# open-race-scale-pi-zero-board-v_04.net
KiCad netlist of a schematic drawn in EAGLE
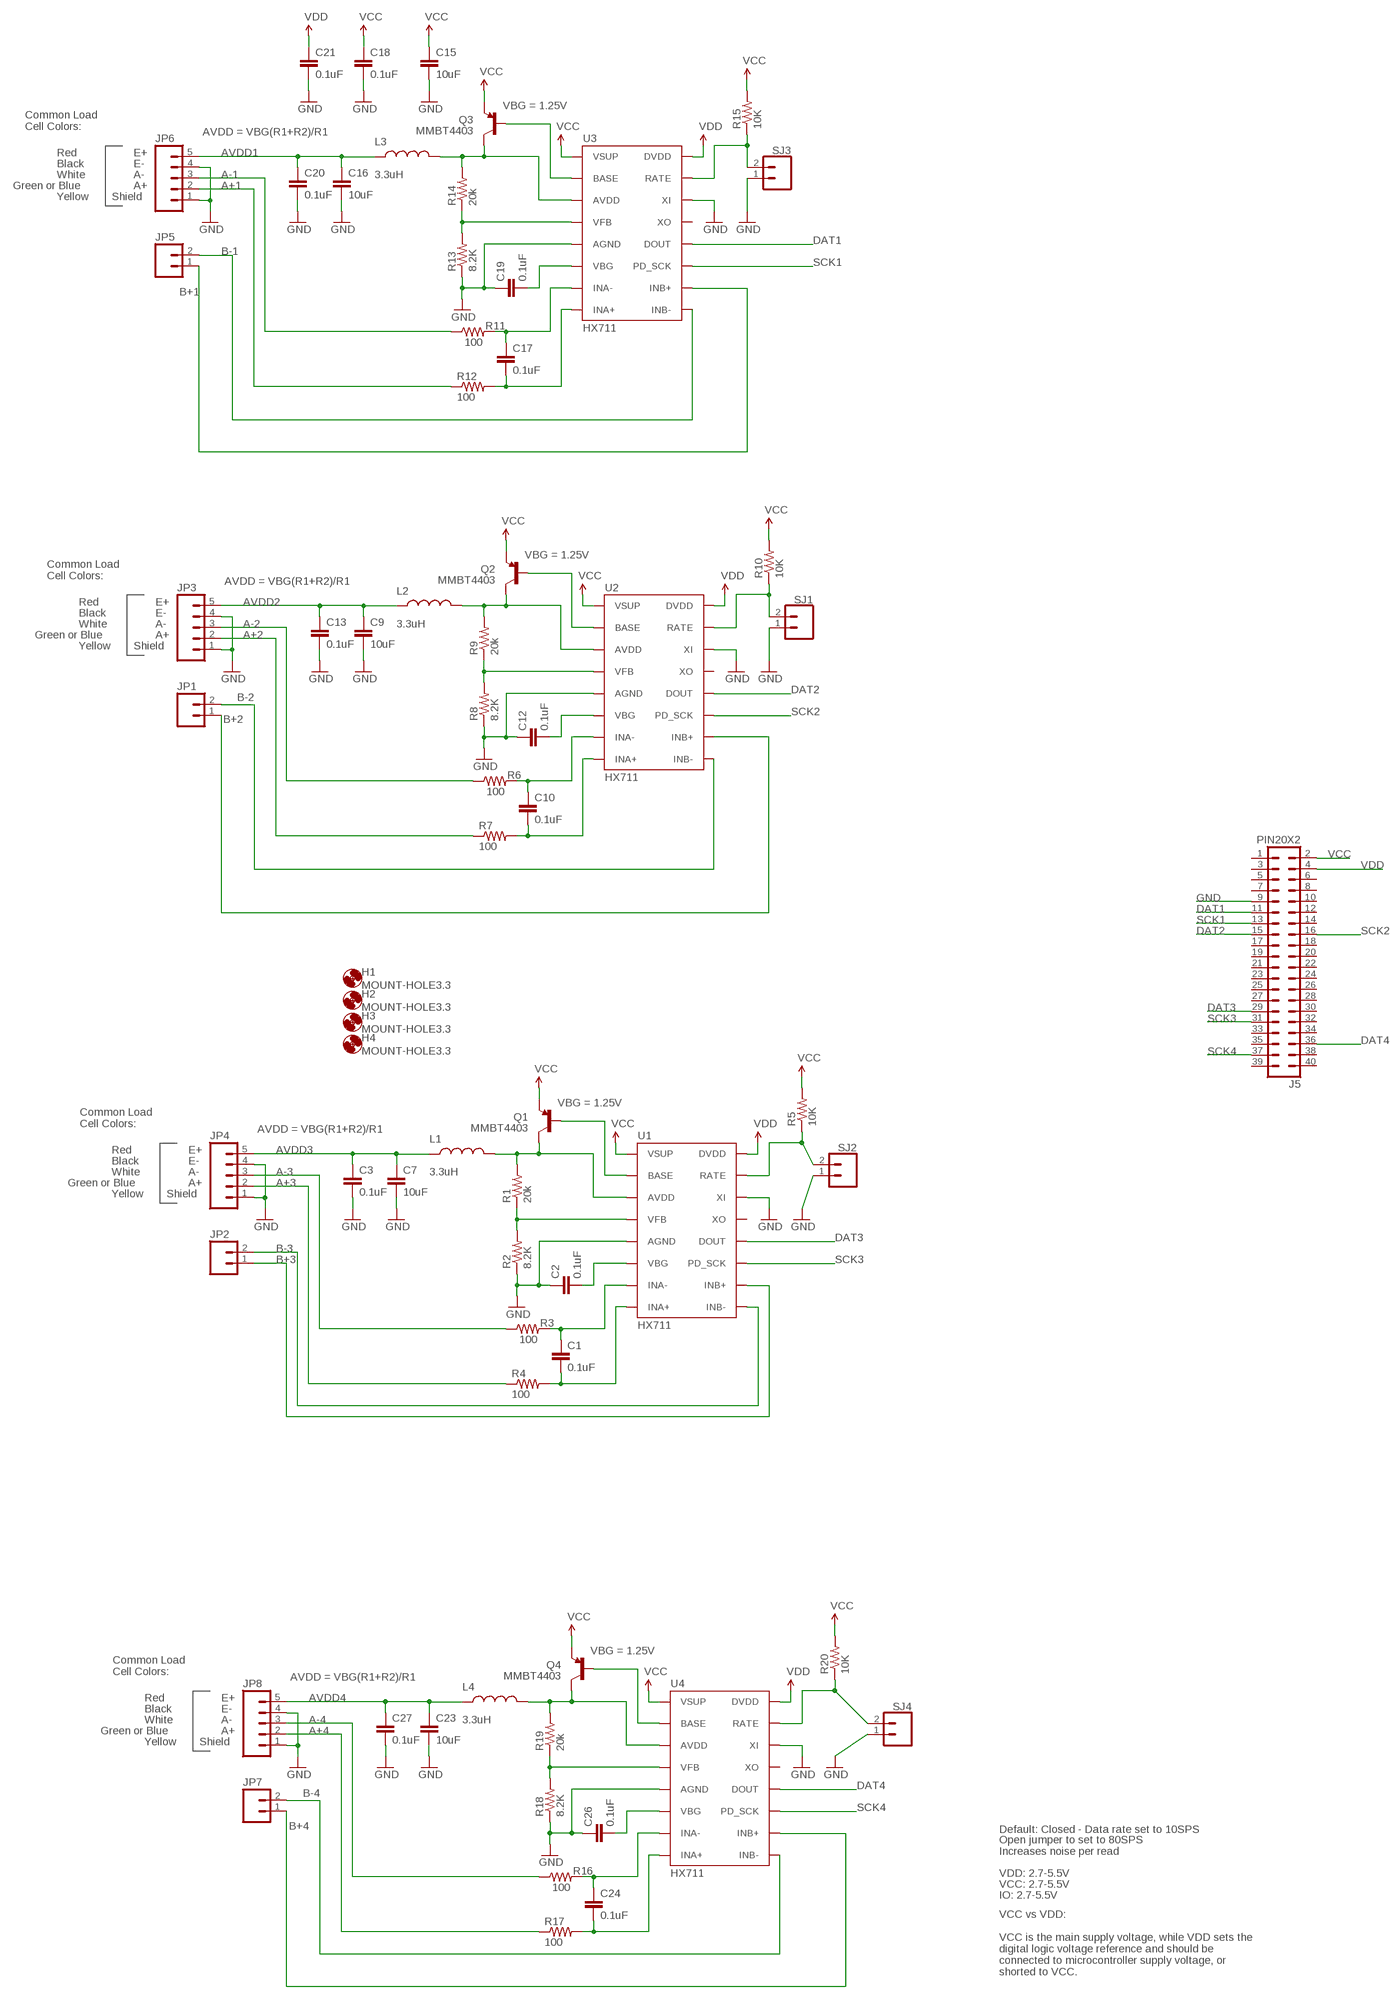
[diagram p0: schematic, sheet 1]

(export (version "E")
  (design (tool "Eeschema 10.0.6"))
  (components
    (comp (ref "C1")
      (value "0.1uF")
      (footprint "eagle-import:0603-CAP")
      (libsource (lib "eagle-import") (part "0.1UF-25V-5%(0603)"))
    )
    (comp (ref "C2")
      (value "0.1uF")
      (footprint "eagle-import:0603-CAP")
      (libsource (lib "eagle-import") (part "0.1UF-25V-5%(0603)"))
    )
    (comp (ref "C3")
      (value "0.1uF")
      (footprint "eagle-import:0603-CAP")
      (libsource (lib "eagle-import") (part "0.1UF-25V-5%(0603)"))
    )
    (comp (ref "C7")
      (value "10uF")
      (footprint "eagle-import:1210")
      (libsource (lib "eagle-import") (part "10UF50V20%(1210)"))
    )
    (comp (ref "C9")
      (value "10uF")
      (footprint "eagle-import:1210")
      (libsource (lib "eagle-import") (part "10UF50V20%(1210)"))
    )
    (comp (ref "C10")
      (value "0.1uF")
      (footprint "eagle-import:0603-CAP")
      (libsource (lib "eagle-import") (part "0.1UF-25V-5%(0603)"))
    )
    (comp (ref "C12")
      (value "0.1uF")
      (footprint "eagle-import:0603-CAP")
      (libsource (lib "eagle-import") (part "0.1UF-25V-5%(0603)"))
    )
    (comp (ref "C13")
      (value "0.1uF")
      (footprint "eagle-import:0603-CAP")
      (libsource (lib "eagle-import") (part "0.1UF-25V-5%(0603)"))
    )
    (comp (ref "C15")
      (value "10uF")
      (footprint "eagle-import:1210")
      (libsource (lib "eagle-import") (part "10UF50V20%(1210)"))
    )
    (comp (ref "C16")
      (value "10uF")
      (footprint "eagle-import:1210")
      (libsource (lib "eagle-import") (part "10UF50V20%(1210)"))
    )
    (comp (ref "C17")
      (value "0.1uF")
      (footprint "eagle-import:0603-CAP")
      (libsource (lib "eagle-import") (part "0.1UF-25V-5%(0603)"))
    )
    (comp (ref "C18")
      (value "0.1uF")
      (footprint "eagle-import:0603-CAP")
      (libsource (lib "eagle-import") (part "0.1UF-25V-5%(0603)"))
    )
    (comp (ref "C19")
      (value "0.1uF")
      (footprint "eagle-import:0603-CAP")
      (libsource (lib "eagle-import") (part "0.1UF-25V-5%(0603)"))
    )
    (comp (ref "C20")
      (value "0.1uF")
      (footprint "eagle-import:0603-CAP")
      (libsource (lib "eagle-import") (part "0.1UF-25V-5%(0603)"))
    )
    (comp (ref "C21")
      (value "0.1uF")
      (footprint "eagle-import:0603-CAP")
      (libsource (lib "eagle-import") (part "0.1UF-25V-5%(0603)"))
    )
    (comp (ref "C23")
      (value "10uF")
      (footprint "eagle-import:1210")
      (libsource (lib "eagle-import") (part "10UF50V20%(1210)"))
    )
    (comp (ref "C24")
      (value "0.1uF")
      (footprint "eagle-import:0603-CAP")
      (libsource (lib "eagle-import") (part "0.1UF-25V-5%(0603)"))
    )
    (comp (ref "C26")
      (value "0.1uF")
      (footprint "eagle-import:0603-CAP")
      (libsource (lib "eagle-import") (part "0.1UF-25V-5%(0603)"))
    )
    (comp (ref "C27")
      (value "0.1uF")
      (footprint "eagle-import:0603-CAP")
      (libsource (lib "eagle-import") (part "0.1UF-25V-5%(0603)"))
    )
    (comp (ref "H1")
      (value "MOUNT-HOLE3.3")
      (footprint "eagle-import:3,3")
      (libsource (lib "eagle-import") (part "MOUNT-HOLE3.3"))
    )
    (comp (ref "H2")
      (value "MOUNT-HOLE3.3")
      (footprint "eagle-import:3,3")
      (libsource (lib "eagle-import") (part "MOUNT-HOLE3.3"))
    )
    (comp (ref "H3")
      (value "MOUNT-HOLE3.3")
      (footprint "eagle-import:3,3")
      (libsource (lib "eagle-import") (part "MOUNT-HOLE3.3"))
    )
    (comp (ref "H4")
      (value "MOUNT-HOLE3.3")
      (footprint "eagle-import:3,3")
      (libsource (lib "eagle-import") (part "MOUNT-HOLE3.3"))
    )
    (comp (ref "J5")
      (value "PIN20X2")
      (footprint "eagle-import:PIN_20X2")
      (libsource (lib "eagle-import") (part "PIN20X2"))
    )
    (comp (ref "JP1")
      (value "M02PTH")
      (footprint "eagle-import:1X02@1")
      (libsource (lib "eagle-import") (part "M02PTH"))
    )
    (comp (ref "JP2")
      (value "M02PTH")
      (footprint "eagle-import:1X02@1")
      (libsource (lib "eagle-import") (part "M02PTH"))
    )
    (comp (ref "JP3")
      (value "M05PTH")
      (footprint "eagle-import:1X05")
      (libsource (lib "eagle-import") (part "M05PTH"))
    )
    (comp (ref "JP4")
      (value "M05PTH")
      (footprint "eagle-import:1X05")
      (libsource (lib "eagle-import") (part "M05PTH"))
    )
    (comp (ref "JP5")
      (value "M02PTH")
      (footprint "eagle-import:1X02@1")
      (libsource (lib "eagle-import") (part "M02PTH"))
    )
    (comp (ref "JP6")
      (value "M05PTH")
      (footprint "eagle-import:1X05")
      (libsource (lib "eagle-import") (part "M05PTH"))
    )
    (comp (ref "JP7")
      (value "M02PTH")
      (footprint "eagle-import:1X02@1")
      (libsource (lib "eagle-import") (part "M02PTH"))
    )
    (comp (ref "JP8")
      (value "M05PTH")
      (footprint "eagle-import:1X05")
      (libsource (lib "eagle-import") (part "M05PTH"))
    )
    (comp (ref "L1")
      (value "3.3uH")
      (footprint "eagle-import:0805")
      (libsource (lib "eagle-import") (part "INDUCTOR0805-IND"))
    )
    (comp (ref "L2")
      (value "3.3uH")
      (footprint "eagle-import:0805")
      (libsource (lib "eagle-import") (part "INDUCTOR0805-IND"))
    )
    (comp (ref "L3")
      (value "3.3uH")
      (footprint "eagle-import:0805")
      (libsource (lib "eagle-import") (part "INDUCTOR0805-IND"))
    )
    (comp (ref "L4")
      (value "3.3uH")
      (footprint "eagle-import:0805")
      (libsource (lib "eagle-import") (part "INDUCTOR0805-IND"))
    )
    (comp (ref "Q1")
      (value "MMBT4403")
      (footprint "eagle-import:SOT23-3")
      (libsource (lib "eagle-import") (part "TRANSISTOR_PNPMMBT4403"))
    )
    (comp (ref "Q2")
      (value "MMBT4403")
      (footprint "eagle-import:SOT23-3")
      (libsource (lib "eagle-import") (part "TRANSISTOR_PNPMMBT4403"))
    )
    (comp (ref "Q3")
      (value "MMBT4403")
      (footprint "eagle-import:SOT23-3")
      (libsource (lib "eagle-import") (part "TRANSISTOR_PNPMMBT4403"))
    )
    (comp (ref "Q4")
      (value "MMBT4403")
      (footprint "eagle-import:SOT23-3")
      (libsource (lib "eagle-import") (part "TRANSISTOR_PNPMMBT4403"))
    )
    (comp (ref "R1")
      (value "20k")
      (footprint "eagle-import:0603-RES")
      (libsource (lib "eagle-import") (part "20KOHM1/10W1%(0603)"))
    )
    (comp (ref "R2")
      (value "8.2K")
      (footprint "eagle-import:0603-RES")
      (libsource (lib "eagle-import") (part "8.2KOHM-1/10W-5%(0603)"))
    )
    (comp (ref "R3")
      (value "100")
      (footprint "eagle-import:0603-RES")
      (libsource (lib "eagle-import") (part "100OHM-1/10W-1%(0603)"))
    )
    (comp (ref "R4")
      (value "100")
      (footprint "eagle-import:0603-RES")
      (libsource (lib "eagle-import") (part "100OHM-1/10W-1%(0603)"))
    )
    (comp (ref "R5")
      (value "10K")
      (footprint "eagle-import:0603-RES")
      (libsource (lib "eagle-import") (part "10KOHM-1/10W-1%(0603)0603"))
    )
    (comp (ref "R6")
      (value "100")
      (footprint "eagle-import:0603-RES")
      (libsource (lib "eagle-import") (part "100OHM-1/10W-1%(0603)"))
    )
    (comp (ref "R7")
      (value "100")
      (footprint "eagle-import:0603-RES")
      (libsource (lib "eagle-import") (part "100OHM-1/10W-1%(0603)"))
    )
    (comp (ref "R8")
      (value "8.2K")
      (footprint "eagle-import:0603-RES")
      (libsource (lib "eagle-import") (part "8.2KOHM-1/10W-5%(0603)"))
    )
    (comp (ref "R9")
      (value "20k")
      (footprint "eagle-import:0603-RES")
      (libsource (lib "eagle-import") (part "20KOHM1/10W1%(0603)"))
    )
    (comp (ref "R10")
      (value "10K")
      (footprint "eagle-import:0603-RES")
      (libsource (lib "eagle-import") (part "10KOHM-1/10W-1%(0603)0603"))
    )
    (comp (ref "R11")
      (value "100")
      (footprint "eagle-import:0603-RES")
      (libsource (lib "eagle-import") (part "100OHM-1/10W-1%(0603)"))
    )
    (comp (ref "R12")
      (value "100")
      (footprint "eagle-import:0603-RES")
      (libsource (lib "eagle-import") (part "100OHM-1/10W-1%(0603)"))
    )
    (comp (ref "R13")
      (value "8.2K")
      (footprint "eagle-import:0603-RES")
      (libsource (lib "eagle-import") (part "8.2KOHM-1/10W-5%(0603)"))
    )
    (comp (ref "R14")
      (value "20k")
      (footprint "eagle-import:0603-RES")
      (libsource (lib "eagle-import") (part "20KOHM1/10W1%(0603)"))
    )
    (comp (ref "R15")
      (value "10K")
      (footprint "eagle-import:0603-RES")
      (libsource (lib "eagle-import") (part "10KOHM-1/10W-1%(0603)0603"))
    )
    (comp (ref "R16")
      (value "100")
      (footprint "eagle-import:0603-RES")
      (libsource (lib "eagle-import") (part "100OHM-1/10W-1%(0603)"))
    )
    (comp (ref "R17")
      (value "100")
      (footprint "eagle-import:0603-RES")
      (libsource (lib "eagle-import") (part "100OHM-1/10W-1%(0603)"))
    )
    (comp (ref "R18")
      (value "8.2K")
      (footprint "eagle-import:0603-RES")
      (libsource (lib "eagle-import") (part "8.2KOHM-1/10W-5%(0603)"))
    )
    (comp (ref "R19")
      (value "20k")
      (footprint "eagle-import:0603-RES")
      (libsource (lib "eagle-import") (part "20KOHM1/10W1%(0603)"))
    )
    (comp (ref "R20")
      (value "10K")
      (footprint "eagle-import:0603-RES")
      (libsource (lib "eagle-import") (part "10KOHM-1/10W-1%(0603)0603"))
    )
    (comp (ref "SJ1")
      (value "CONN_02")
      (footprint "eagle-import:1X02")
      (libsource (lib "eagle-import") (part "CONN_02"))
    )
    (comp (ref "SJ2")
      (value "CONN_02")
      (footprint "eagle-import:1X02")
      (libsource (lib "eagle-import") (part "CONN_02"))
    )
    (comp (ref "SJ3")
      (value "CONN_02")
      (footprint "eagle-import:1X02")
      (libsource (lib "eagle-import") (part "CONN_02"))
    )
    (comp (ref "SJ4")
      (value "CONN_02")
      (footprint "eagle-import:1X02")
      (libsource (lib "eagle-import") (part "CONN_02"))
    )
    (comp (ref "U1")
      (value "HX711")
      (footprint "eagle-import:SO16")
      (libsource (lib "eagle-import") (part "HX711HX711"))
    )
    (comp (ref "U2")
      (value "HX711")
      (footprint "eagle-import:SO16")
      (libsource (lib "eagle-import") (part "HX711HX711"))
    )
    (comp (ref "U3")
      (value "HX711")
      (footprint "eagle-import:SO16")
      (libsource (lib "eagle-import") (part "HX711HX711"))
    )
    (comp (ref "U4")
      (value "HX711")
      (footprint "eagle-import:SO16")
      (libsource (lib "eagle-import") (part "HX711HX711"))
    )
  )
  (nets
    (net (code "1") (name "/A+1") (class "Default")
      (node (ref "JP6") (pin "2") (pinfunction "2_2") (pintype "passive"))
      (node (ref "R12") (pin "1") (pinfunction "1_1") (pintype "passive"))
    )
    (net (code "2") (name "/A+2") (class "Default")
      (node (ref "JP3") (pin "2") (pinfunction "2_2") (pintype "passive"))
      (node (ref "R7") (pin "1") (pinfunction "1_1") (pintype "passive"))
    )
    (net (code "3") (name "/A+3") (class "Default")
      (node (ref "JP4") (pin "2") (pinfunction "2_2") (pintype "passive"))
      (node (ref "R4") (pin "1") (pinfunction "1_1") (pintype "passive"))
    )
    (net (code "4") (name "/A+4") (class "Default")
      (node (ref "JP8") (pin "2") (pinfunction "2_2") (pintype "passive"))
      (node (ref "R17") (pin "1") (pinfunction "1_1") (pintype "passive"))
    )
    (net (code "5") (name "/A-1") (class "Default")
      (node (ref "JP6") (pin "3") (pinfunction "3_3") (pintype "passive"))
      (node (ref "R11") (pin "1") (pinfunction "1_1") (pintype "passive"))
    )
    (net (code "6") (name "/A-2") (class "Default")
      (node (ref "JP3") (pin "3") (pinfunction "3_3") (pintype "passive"))
      (node (ref "R6") (pin "1") (pinfunction "1_1") (pintype "passive"))
    )
    (net (code "7") (name "/A-3") (class "Default")
      (node (ref "JP4") (pin "3") (pinfunction "3_3") (pintype "passive"))
      (node (ref "R3") (pin "1") (pinfunction "1_1") (pintype "passive"))
    )
    (net (code "8") (name "/A-4") (class "Default")
      (node (ref "JP8") (pin "3") (pinfunction "3_3") (pintype "passive"))
      (node (ref "R16") (pin "1") (pinfunction "1_1") (pintype "passive"))
    )
    (net (code "9") (name "/AVDD1") (class "Default")
      (node (ref "C16") (pin "1") (pinfunction "1_1") (pintype "passive"))
      (node (ref "C20") (pin "1") (pinfunction "1_1") (pintype "passive"))
      (node (ref "JP6") (pin "5") (pinfunction "5_5") (pintype "passive"))
      (node (ref "L3") (pin "1") (pinfunction "1_1") (pintype "passive"))
    )
    (net (code "10") (name "/AVDD2") (class "Default")
      (node (ref "C13") (pin "1") (pinfunction "1_1") (pintype "passive"))
      (node (ref "C9") (pin "1") (pinfunction "1_1") (pintype "passive"))
      (node (ref "JP3") (pin "5") (pinfunction "5_5") (pintype "passive"))
      (node (ref "L2") (pin "1") (pinfunction "1_1") (pintype "passive"))
    )
    (net (code "11") (name "/AVDD3") (class "Default")
      (node (ref "C3") (pin "1") (pinfunction "1_1") (pintype "passive"))
      (node (ref "C7") (pin "1") (pinfunction "1_1") (pintype "passive"))
      (node (ref "JP4") (pin "5") (pinfunction "5_5") (pintype "passive"))
      (node (ref "L1") (pin "1") (pinfunction "1_1") (pintype "passive"))
    )
    (net (code "12") (name "/AVDD4") (class "Default")
      (node (ref "C23") (pin "1") (pinfunction "1_1") (pintype "passive"))
      (node (ref "C27") (pin "1") (pinfunction "1_1") (pintype "passive"))
      (node (ref "JP8") (pin "5") (pinfunction "5_5") (pintype "passive"))
      (node (ref "L4") (pin "1") (pinfunction "1_1") (pintype "passive"))
    )
    (net (code "13") (name "/B+1") (class "Default")
      (node (ref "JP5") (pin "1") (pinfunction "1_1") (pintype "passive"))
      (node (ref "U3") (pin "10") (pinfunction "INB+_10") (pintype "bidirectional"))
    )
    (net (code "14") (name "/B+2") (class "Default")
      (node (ref "JP1") (pin "1") (pinfunction "1_1") (pintype "passive"))
      (node (ref "U2") (pin "10") (pinfunction "INB+_10") (pintype "bidirectional"))
    )
    (net (code "15") (name "/B+3") (class "Default")
      (node (ref "JP2") (pin "1") (pinfunction "1_1") (pintype "passive"))
      (node (ref "U1") (pin "10") (pinfunction "INB+_10") (pintype "bidirectional"))
    )
    (net (code "16") (name "/B+4") (class "Default")
      (node (ref "JP7") (pin "1") (pinfunction "1_1") (pintype "passive"))
      (node (ref "U4") (pin "10") (pinfunction "INB+_10") (pintype "bidirectional"))
    )
    (net (code "17") (name "/B-1") (class "Default")
      (node (ref "JP5") (pin "2") (pinfunction "2_2") (pintype "passive"))
      (node (ref "U3") (pin "9") (pinfunction "INB-_9") (pintype "bidirectional"))
    )
    (net (code "18") (name "/B-2") (class "Default")
      (node (ref "JP1") (pin "2") (pinfunction "2_2") (pintype "passive"))
      (node (ref "U2") (pin "9") (pinfunction "INB-_9") (pintype "bidirectional"))
    )
    (net (code "19") (name "/B-3") (class "Default")
      (node (ref "JP2") (pin "2") (pinfunction "2_2") (pintype "passive"))
      (node (ref "U1") (pin "9") (pinfunction "INB-_9") (pintype "bidirectional"))
    )
    (net (code "20") (name "/B-4") (class "Default")
      (node (ref "JP7") (pin "2") (pinfunction "2_2") (pintype "passive"))
      (node (ref "U4") (pin "9") (pinfunction "INB-_9") (pintype "bidirectional"))
    )
    (net (code "21") (name "/DAT1") (class "Default")
      (node (ref "J5") (pin "11") (pinfunction "11_11") (pintype "passive"))
      (node (ref "U3") (pin "12") (pinfunction "DOUT_12") (pintype "bidirectional"))
    )
    (net (code "22") (name "/DAT2") (class "Default")
      (node (ref "J5") (pin "15") (pinfunction "15_15") (pintype "passive"))
      (node (ref "U2") (pin "12") (pinfunction "DOUT_12") (pintype "bidirectional"))
    )
    (net (code "23") (name "/DAT3") (class "Default")
      (node (ref "J5") (pin "29") (pinfunction "29_29") (pintype "passive"))
      (node (ref "U1") (pin "12") (pinfunction "DOUT_12") (pintype "bidirectional"))
    )
    (net (code "24") (name "/DAT4") (class "Default")
      (node (ref "J5") (pin "36") (pinfunction "36_36") (pintype "passive"))
      (node (ref "U4") (pin "12") (pinfunction "DOUT_12") (pintype "bidirectional"))
    )
    (net (code "25") (name "/SCK1") (class "Default")
      (node (ref "J5") (pin "13") (pinfunction "13_13") (pintype "passive"))
      (node (ref "U3") (pin "11") (pinfunction "PD_SCK_11") (pintype "bidirectional"))
    )
    (net (code "26") (name "/SCK2") (class "Default")
      (node (ref "J5") (pin "16") (pinfunction "16_16") (pintype "passive"))
      (node (ref "U2") (pin "11") (pinfunction "PD_SCK_11") (pintype "bidirectional"))
    )
    (net (code "27") (name "/SCK3") (class "Default")
      (node (ref "J5") (pin "31") (pinfunction "31_31") (pintype "passive"))
      (node (ref "U1") (pin "11") (pinfunction "PD_SCK_11") (pintype "bidirectional"))
    )
    (net (code "28") (name "/SCK4") (class "Default")
      (node (ref "J5") (pin "37") (pinfunction "37_37") (pintype "passive"))
      (node (ref "U4") (pin "11") (pinfunction "PD_SCK_11") (pintype "bidirectional"))
    )
    (net (code "29") (name "GND") (class "Default")
      (node (ref "C12") (pin "1") (pinfunction "1_1") (pintype "passive"))
      (node (ref "C13") (pin "2") (pinfunction "2_2") (pintype "passive"))
      (node (ref "C15") (pin "2") (pinfunction "2_2") (pintype "passive"))
      (node (ref "C16") (pin "2") (pinfunction "2_2") (pintype "passive"))
      (node (ref "C18") (pin "2") (pinfunction "2_2") (pintype "passive"))
      (node (ref "C19") (pin "1") (pinfunction "1_1") (pintype "passive"))
      (node (ref "C2") (pin "1") (pinfunction "1_1") (pintype "passive"))
      (node (ref "C20") (pin "2") (pinfunction "2_2") (pintype "passive"))
      (node (ref "C21") (pin "2") (pinfunction "2_2") (pintype "passive"))
      (node (ref "C23") (pin "2") (pinfunction "2_2") (pintype "passive"))
      (node (ref "C26") (pin "1") (pinfunction "1_1") (pintype "passive"))
      (node (ref "C27") (pin "2") (pinfunction "2_2") (pintype "passive"))
      (node (ref "C3") (pin "2") (pinfunction "2_2") (pintype "passive"))
      (node (ref "C7") (pin "2") (pinfunction "2_2") (pintype "passive"))
      (node (ref "C9") (pin "2") (pinfunction "2_2") (pintype "passive"))
      (node (ref "J5") (pin "9") (pinfunction "9_9") (pintype "passive"))
      (node (ref "JP3") (pin "1") (pinfunction "1_1") (pintype "passive"))
      (node (ref "JP3") (pin "4") (pinfunction "4_4") (pintype "passive"))
      (node (ref "JP4") (pin "1") (pinfunction "1_1") (pintype "passive"))
      (node (ref "JP4") (pin "4") (pinfunction "4_4") (pintype "passive"))
      (node (ref "JP6") (pin "1") (pinfunction "1_1") (pintype "passive"))
      (node (ref "JP6") (pin "4") (pinfunction "4_4") (pintype "passive"))
      (node (ref "JP8") (pin "1") (pinfunction "1_1") (pintype "passive"))
      (node (ref "JP8") (pin "4") (pinfunction "4_4") (pintype "passive"))
      (node (ref "R13") (pin "1") (pinfunction "1_1") (pintype "passive"))
      (node (ref "R18") (pin "1") (pinfunction "1_1") (pintype "passive"))
      (node (ref "R2") (pin "1") (pinfunction "1_1") (pintype "passive"))
      (node (ref "R8") (pin "1") (pinfunction "1_1") (pintype "passive"))
      (node (ref "SJ1") (pin "1") (pinfunction "1_1") (pintype "passive"))
      (node (ref "SJ2") (pin "1") (pinfunction "1_1") (pintype "passive"))
      (node (ref "SJ3") (pin "1") (pinfunction "1_1") (pintype "passive"))
      (node (ref "SJ4") (pin "1") (pinfunction "1_1") (pintype "passive"))
      (node (ref "U1") (pin "14") (pinfunction "XI_14") (pintype "bidirectional"))
      (node (ref "U1") (pin "5") (pinfunction "AGND_5") (pintype "bidirectional"))
      (node (ref "U2") (pin "14") (pinfunction "XI_14") (pintype "bidirectional"))
      (node (ref "U2") (pin "5") (pinfunction "AGND_5") (pintype "bidirectional"))
      (node (ref "U3") (pin "14") (pinfunction "XI_14") (pintype "bidirectional"))
      (node (ref "U3") (pin "5") (pinfunction "AGND_5") (pintype "bidirectional"))
      (node (ref "U4") (pin "14") (pinfunction "XI_14") (pintype "bidirectional"))
      (node (ref "U4") (pin "5") (pinfunction "AGND_5") (pintype "bidirectional"))
    )
    (net (code "30") (name "Net-(Q1-B)") (class "Default")
      (node (ref "Q1") (pin "1") (pinfunction "B_1") (pintype "passive"))
      (node (ref "U1") (pin "2") (pinfunction "BASE_2") (pintype "bidirectional"))
    )
    (net (code "31") (name "Net-(Q1-C)") (class "Default")
      (node (ref "L1") (pin "2") (pinfunction "2_2") (pintype "passive"))
      (node (ref "Q1") (pin "3") (pinfunction "C_3") (pintype "passive"))
      (node (ref "R1") (pin "2") (pinfunction "2_2") (pintype "passive"))
      (node (ref "U1") (pin "3") (pinfunction "AVDD_3") (pintype "bidirectional"))
    )
    (net (code "32") (name "Net-(Q2-B)") (class "Default")
      (node (ref "Q2") (pin "1") (pinfunction "B_1") (pintype "passive"))
      (node (ref "U2") (pin "2") (pinfunction "BASE_2") (pintype "bidirectional"))
    )
    (net (code "33") (name "Net-(Q2-C)") (class "Default")
      (node (ref "L2") (pin "2") (pinfunction "2_2") (pintype "passive"))
      (node (ref "Q2") (pin "3") (pinfunction "C_3") (pintype "passive"))
      (node (ref "R9") (pin "2") (pinfunction "2_2") (pintype "passive"))
      (node (ref "U2") (pin "3") (pinfunction "AVDD_3") (pintype "bidirectional"))
    )
    (net (code "34") (name "Net-(Q3-B)") (class "Default")
      (node (ref "Q3") (pin "1") (pinfunction "B_1") (pintype "passive"))
      (node (ref "U3") (pin "2") (pinfunction "BASE_2") (pintype "bidirectional"))
    )
    (net (code "35") (name "Net-(Q3-C)") (class "Default")
      (node (ref "L3") (pin "2") (pinfunction "2_2") (pintype "passive"))
      (node (ref "Q3") (pin "3") (pinfunction "C_3") (pintype "passive"))
      (node (ref "R14") (pin "2") (pinfunction "2_2") (pintype "passive"))
      (node (ref "U3") (pin "3") (pinfunction "AVDD_3") (pintype "bidirectional"))
    )
    (net (code "36") (name "Net-(Q4-B)") (class "Default")
      (node (ref "Q4") (pin "1") (pinfunction "B_1") (pintype "passive"))
      (node (ref "U4") (pin "2") (pinfunction "BASE_2") (pintype "bidirectional"))
    )
    (net (code "37") (name "Net-(Q4-C)") (class "Default")
      (node (ref "L4") (pin "2") (pinfunction "2_2") (pintype "passive"))
      (node (ref "Q4") (pin "3") (pinfunction "C_3") (pintype "passive"))
      (node (ref "R19") (pin "2") (pinfunction "2_2") (pintype "passive"))
      (node (ref "U4") (pin "3") (pinfunction "AVDD_3") (pintype "bidirectional"))
    )
    (net (code "38") (name "Net-(U1-INA+)") (class "Default")
      (node (ref "C1") (pin "2") (pinfunction "2_2") (pintype "passive"))
      (node (ref "R4") (pin "2") (pinfunction "2_2") (pintype "passive"))
      (node (ref "U1") (pin "8") (pinfunction "INA+_8") (pintype "bidirectional"))
    )
    (net (code "39") (name "Net-(U1-INA-)") (class "Default")
      (node (ref "C1") (pin "1") (pinfunction "1_1") (pintype "passive"))
      (node (ref "R3") (pin "2") (pinfunction "2_2") (pintype "passive"))
      (node (ref "U1") (pin "7") (pinfunction "INA-_7") (pintype "bidirectional"))
    )
    (net (code "40") (name "Net-(U1-RATE)") (class "Default")
      (node (ref "R5") (pin "1") (pinfunction "1_1") (pintype "passive"))
      (node (ref "SJ2") (pin "2") (pinfunction "2_2") (pintype "passive"))
      (node (ref "U1") (pin "15") (pinfunction "RATE_15") (pintype "bidirectional"))
    )
    (net (code "41") (name "Net-(U1-VBG)") (class "Default")
      (node (ref "C2") (pin "2") (pinfunction "2_2") (pintype "passive"))
      (node (ref "U1") (pin "6") (pinfunction "VBG_6") (pintype "bidirectional"))
    )
    (net (code "42") (name "Net-(U1-VFB)") (class "Default")
      (node (ref "R1") (pin "1") (pinfunction "1_1") (pintype "passive"))
      (node (ref "R2") (pin "2") (pinfunction "2_2") (pintype "passive"))
      (node (ref "U1") (pin "4") (pinfunction "VFB_4") (pintype "bidirectional"))
    )
    (net (code "43") (name "Net-(U2-INA+)") (class "Default")
      (node (ref "C10") (pin "2") (pinfunction "2_2") (pintype "passive"))
      (node (ref "R7") (pin "2") (pinfunction "2_2") (pintype "passive"))
      (node (ref "U2") (pin "8") (pinfunction "INA+_8") (pintype "bidirectional"))
    )
    (net (code "44") (name "Net-(U2-INA-)") (class "Default")
      (node (ref "C10") (pin "1") (pinfunction "1_1") (pintype "passive"))
      (node (ref "R6") (pin "2") (pinfunction "2_2") (pintype "passive"))
      (node (ref "U2") (pin "7") (pinfunction "INA-_7") (pintype "bidirectional"))
    )
    (net (code "45") (name "Net-(U2-RATE)") (class "Default")
      (node (ref "R10") (pin "1") (pinfunction "1_1") (pintype "passive"))
      (node (ref "SJ1") (pin "2") (pinfunction "2_2") (pintype "passive"))
      (node (ref "U2") (pin "15") (pinfunction "RATE_15") (pintype "bidirectional"))
    )
    (net (code "46") (name "Net-(U2-VBG)") (class "Default")
      (node (ref "C12") (pin "2") (pinfunction "2_2") (pintype "passive"))
      (node (ref "U2") (pin "6") (pinfunction "VBG_6") (pintype "bidirectional"))
    )
    (net (code "47") (name "Net-(U2-VFB)") (class "Default")
      (node (ref "R8") (pin "2") (pinfunction "2_2") (pintype "passive"))
      (node (ref "R9") (pin "1") (pinfunction "1_1") (pintype "passive"))
      (node (ref "U2") (pin "4") (pinfunction "VFB_4") (pintype "bidirectional"))
    )
    (net (code "48") (name "Net-(U3-INA+)") (class "Default")
      (node (ref "C17") (pin "2") (pinfunction "2_2") (pintype "passive"))
      (node (ref "R12") (pin "2") (pinfunction "2_2") (pintype "passive"))
      (node (ref "U3") (pin "8") (pinfunction "INA+_8") (pintype "bidirectional"))
    )
    (net (code "49") (name "Net-(U3-INA-)") (class "Default")
      (node (ref "C17") (pin "1") (pinfunction "1_1") (pintype "passive"))
      (node (ref "R11") (pin "2") (pinfunction "2_2") (pintype "passive"))
      (node (ref "U3") (pin "7") (pinfunction "INA-_7") (pintype "bidirectional"))
    )
    (net (code "50") (name "Net-(U3-RATE)") (class "Default")
      (node (ref "R15") (pin "1") (pinfunction "1_1") (pintype "passive"))
      (node (ref "SJ3") (pin "2") (pinfunction "2_2") (pintype "passive"))
      (node (ref "U3") (pin "15") (pinfunction "RATE_15") (pintype "bidirectional"))
    )
    (net (code "51") (name "Net-(U3-VBG)") (class "Default")
      (node (ref "C19") (pin "2") (pinfunction "2_2") (pintype "passive"))
      (node (ref "U3") (pin "6") (pinfunction "VBG_6") (pintype "bidirectional"))
    )
    (net (code "52") (name "Net-(U3-VFB)") (class "Default")
      (node (ref "R13") (pin "2") (pinfunction "2_2") (pintype "passive"))
      (node (ref "R14") (pin "1") (pinfunction "1_1") (pintype "passive"))
      (node (ref "U3") (pin "4") (pinfunction "VFB_4") (pintype "bidirectional"))
    )
    (net (code "53") (name "Net-(U4-INA+)") (class "Default")
      (node (ref "C24") (pin "2") (pinfunction "2_2") (pintype "passive"))
      (node (ref "R17") (pin "2") (pinfunction "2_2") (pintype "passive"))
      (node (ref "U4") (pin "8") (pinfunction "INA+_8") (pintype "bidirectional"))
    )
    (net (code "54") (name "Net-(U4-INA-)") (class "Default")
      (node (ref "C24") (pin "1") (pinfunction "1_1") (pintype "passive"))
      (node (ref "R16") (pin "2") (pinfunction "2_2") (pintype "passive"))
      (node (ref "U4") (pin "7") (pinfunction "INA-_7") (pintype "bidirectional"))
    )
    (net (code "55") (name "Net-(U4-RATE)") (class "Default")
      (node (ref "R20") (pin "1") (pinfunction "1_1") (pintype "passive"))
      (node (ref "SJ4") (pin "2") (pinfunction "2_2") (pintype "passive"))
      (node (ref "U4") (pin "15") (pinfunction "RATE_15") (pintype "bidirectional"))
    )
    (net (code "56") (name "Net-(U4-VBG)") (class "Default")
      (node (ref "C26") (pin "2") (pinfunction "2_2") (pintype "passive"))
      (node (ref "U4") (pin "6") (pinfunction "VBG_6") (pintype "bidirectional"))
    )
    (net (code "57") (name "Net-(U4-VFB)") (class "Default")
      (node (ref "R18") (pin "2") (pinfunction "2_2") (pintype "passive"))
      (node (ref "R19") (pin "1") (pinfunction "1_1") (pintype "passive"))
      (node (ref "U4") (pin "4") (pinfunction "VFB_4") (pintype "bidirectional"))
    )
    (net (code "58") (name "VCC") (class "Default")
      (node (ref "C15") (pin "1") (pinfunction "1_1") (pintype "passive"))
      (node (ref "C18") (pin "1") (pinfunction "1_1") (pintype "passive"))
      (node (ref "J5") (pin "2") (pinfunction "2_2") (pintype "passive"))
      (node (ref "Q1") (pin "2") (pinfunction "E_2") (pintype "passive"))
      (node (ref "Q2") (pin "2") (pinfunction "E_2") (pintype "passive"))
      (node (ref "Q3") (pin "2") (pinfunction "E_2") (pintype "passive"))
      (node (ref "Q4") (pin "2") (pinfunction "E_2") (pintype "passive"))
      (node (ref "R10") (pin "2") (pinfunction "2_2") (pintype "passive"))
      (node (ref "R15") (pin "2") (pinfunction "2_2") (pintype "passive"))
      (node (ref "R20") (pin "2") (pinfunction "2_2") (pintype "passive"))
      (node (ref "R5") (pin "2") (pinfunction "2_2") (pintype "passive"))
      (node (ref "U1") (pin "1") (pinfunction "VSUP_1") (pintype "bidirectional"))
      (node (ref "U2") (pin "1") (pinfunction "VSUP_1") (pintype "bidirectional"))
      (node (ref "U3") (pin "1") (pinfunction "VSUP_1") (pintype "bidirectional"))
      (node (ref "U4") (pin "1") (pinfunction "VSUP_1") (pintype "bidirectional"))
    )
    (net (code "59") (name "VDD") (class "Default")
      (node (ref "C21") (pin "1") (pinfunction "1_1") (pintype "passive"))
      (node (ref "J5") (pin "4") (pinfunction "4_4") (pintype "passive"))
      (node (ref "U1") (pin "16") (pinfunction "DVDD_16") (pintype "bidirectional"))
      (node (ref "U2") (pin "16") (pinfunction "DVDD_16") (pintype "bidirectional"))
      (node (ref "U3") (pin "16") (pinfunction "DVDD_16") (pintype "bidirectional"))
      (node (ref "U4") (pin "16") (pinfunction "DVDD_16") (pintype "bidirectional"))
    )
    (net (code "60") (name "unconnected-(J5-Pad1)") (class "Default")
      (node (ref "J5") (pin "1") (pinfunction "1_1") (pintype "passive"))
    )
    (net (code "61") (name "unconnected-(J5-Pad3)") (class "Default")
      (node (ref "J5") (pin "3") (pinfunction "3_3") (pintype "passive"))
    )
    (net (code "62") (name "unconnected-(J5-Pad5)") (class "Default")
      (node (ref "J5") (pin "5") (pinfunction "5_5") (pintype "passive"))
    )
    (net (code "63") (name "unconnected-(J5-Pad6)") (class "Default")
      (node (ref "J5") (pin "6") (pinfunction "6_6") (pintype "passive"))
    )
    (net (code "64") (name "unconnected-(J5-Pad7)") (class "Default")
      (node (ref "J5") (pin "7") (pinfunction "7_7") (pintype "passive"))
    )
    (net (code "65") (name "unconnected-(J5-Pad8)") (class "Default")
      (node (ref "J5") (pin "8") (pinfunction "8_8") (pintype "passive"))
    )
    (net (code "66") (name "unconnected-(J5-Pad10)") (class "Default")
      (node (ref "J5") (pin "10") (pinfunction "10_10") (pintype "passive"))
    )
    (net (code "67") (name "unconnected-(J5-Pad12)") (class "Default")
      (node (ref "J5") (pin "12") (pinfunction "12_12") (pintype "passive"))
    )
    (net (code "68") (name "unconnected-(J5-Pad14)") (class "Default")
      (node (ref "J5") (pin "14") (pinfunction "14_14") (pintype "passive"))
    )
    (net (code "69") (name "unconnected-(J5-Pad17)") (class "Default")
      (node (ref "J5") (pin "17") (pinfunction "17_17") (pintype "passive"))
    )
    (net (code "70") (name "unconnected-(J5-Pad18)") (class "Default")
      (node (ref "J5") (pin "18") (pinfunction "18_18") (pintype "passive"))
    )
    (net (code "71") (name "unconnected-(J5-Pad19)") (class "Default")
      (node (ref "J5") (pin "19") (pinfunction "19_19") (pintype "passive"))
    )
    (net (code "72") (name "unconnected-(J5-Pad20)") (class "Default")
      (node (ref "J5") (pin "20") (pinfunction "20_20") (pintype "passive"))
    )
    (net (code "73") (name "unconnected-(J5-Pad21)") (class "Default")
      (node (ref "J5") (pin "21") (pinfunction "21_21") (pintype "passive"))
    )
    (net (code "74") (name "unconnected-(J5-Pad22)") (class "Default")
      (node (ref "J5") (pin "22") (pinfunction "22_22") (pintype "passive"))
    )
    (net (code "75") (name "unconnected-(J5-Pad23)") (class "Default")
      (node (ref "J5") (pin "23") (pinfunction "23_23") (pintype "passive"))
    )
    (net (code "76") (name "unconnected-(J5-Pad24)") (class "Default")
      (node (ref "J5") (pin "24") (pinfunction "24_24") (pintype "passive"))
    )
    (net (code "77") (name "unconnected-(J5-Pad25)") (class "Default")
      (node (ref "J5") (pin "25") (pinfunction "25_25") (pintype "passive"))
    )
    (net (code "78") (name "unconnected-(J5-Pad26)") (class "Default")
      (node (ref "J5") (pin "26") (pinfunction "26_26") (pintype "passive"))
    )
    (net (code "79") (name "unconnected-(J5-Pad27)") (class "Default")
      (node (ref "J5") (pin "27") (pinfunction "27_27") (pintype "passive"))
    )
    (net (code "80") (name "unconnected-(J5-Pad28)") (class "Default")
      (node (ref "J5") (pin "28") (pinfunction "28_28") (pintype "passive"))
    )
    (net (code "81") (name "unconnected-(J5-Pad30)") (class "Default")
      (node (ref "J5") (pin "30") (pinfunction "30_30") (pintype "passive"))
    )
    (net (code "82") (name "unconnected-(J5-Pad32)") (class "Default")
      (node (ref "J5") (pin "32") (pinfunction "32_32") (pintype "passive"))
    )
    (net (code "83") (name "unconnected-(J5-Pad33)") (class "Default")
      (node (ref "J5") (pin "33") (pinfunction "33_33") (pintype "passive"))
    )
    (net (code "84") (name "unconnected-(J5-Pad34)") (class "Default")
      (node (ref "J5") (pin "34") (pinfunction "34_34") (pintype "passive"))
    )
    (net (code "85") (name "unconnected-(J5-Pad35)") (class "Default")
      (node (ref "J5") (pin "35") (pinfunction "35_35") (pintype "passive"))
    )
    (net (code "86") (name "unconnected-(J5-Pad38)") (class "Default")
      (node (ref "J5") (pin "38") (pinfunction "38_38") (pintype "passive"))
    )
    (net (code "87") (name "unconnected-(J5-Pad39)") (class "Default")
      (node (ref "J5") (pin "39") (pinfunction "39_39") (pintype "passive"))
    )
    (net (code "88") (name "unconnected-(J5-Pad40)") (class "Default")
      (node (ref "J5") (pin "40") (pinfunction "40_40") (pintype "passive"))
    )
    (net (code "89") (name "unconnected-(U1-XO-Pad13)") (class "Default")
      (node (ref "U1") (pin "13") (pinfunction "XO_13") (pintype "bidirectional"))
    )
    (net (code "90") (name "unconnected-(U2-XO-Pad13)") (class "Default")
      (node (ref "U2") (pin "13") (pinfunction "XO_13") (pintype "bidirectional"))
    )
    (net (code "91") (name "unconnected-(U3-XO-Pad13)") (class "Default")
      (node (ref "U3") (pin "13") (pinfunction "XO_13") (pintype "bidirectional"))
    )
    (net (code "92") (name "unconnected-(U4-XO-Pad13)") (class "Default")
      (node (ref "U4") (pin "13") (pinfunction "XO_13") (pintype "bidirectional"))
    )
  )
)
